# ADC.net
KiCad netlist of a schematic drawn in Altium Designer
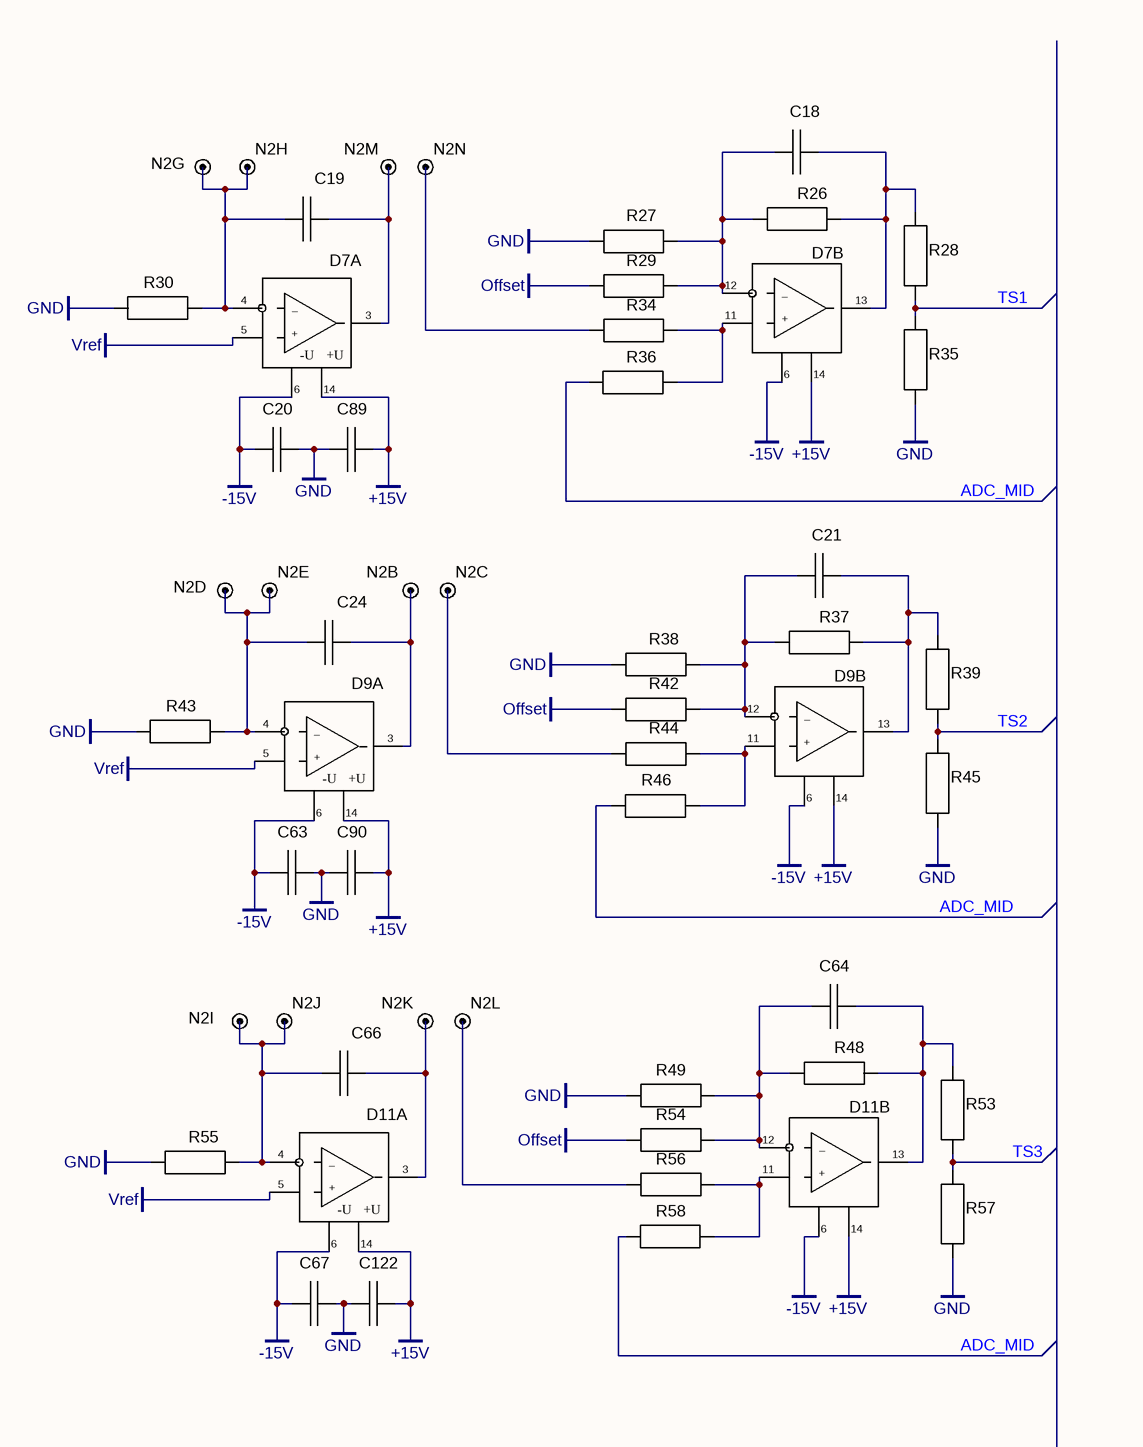
[diagram p0: ADC.SchDoc, top]
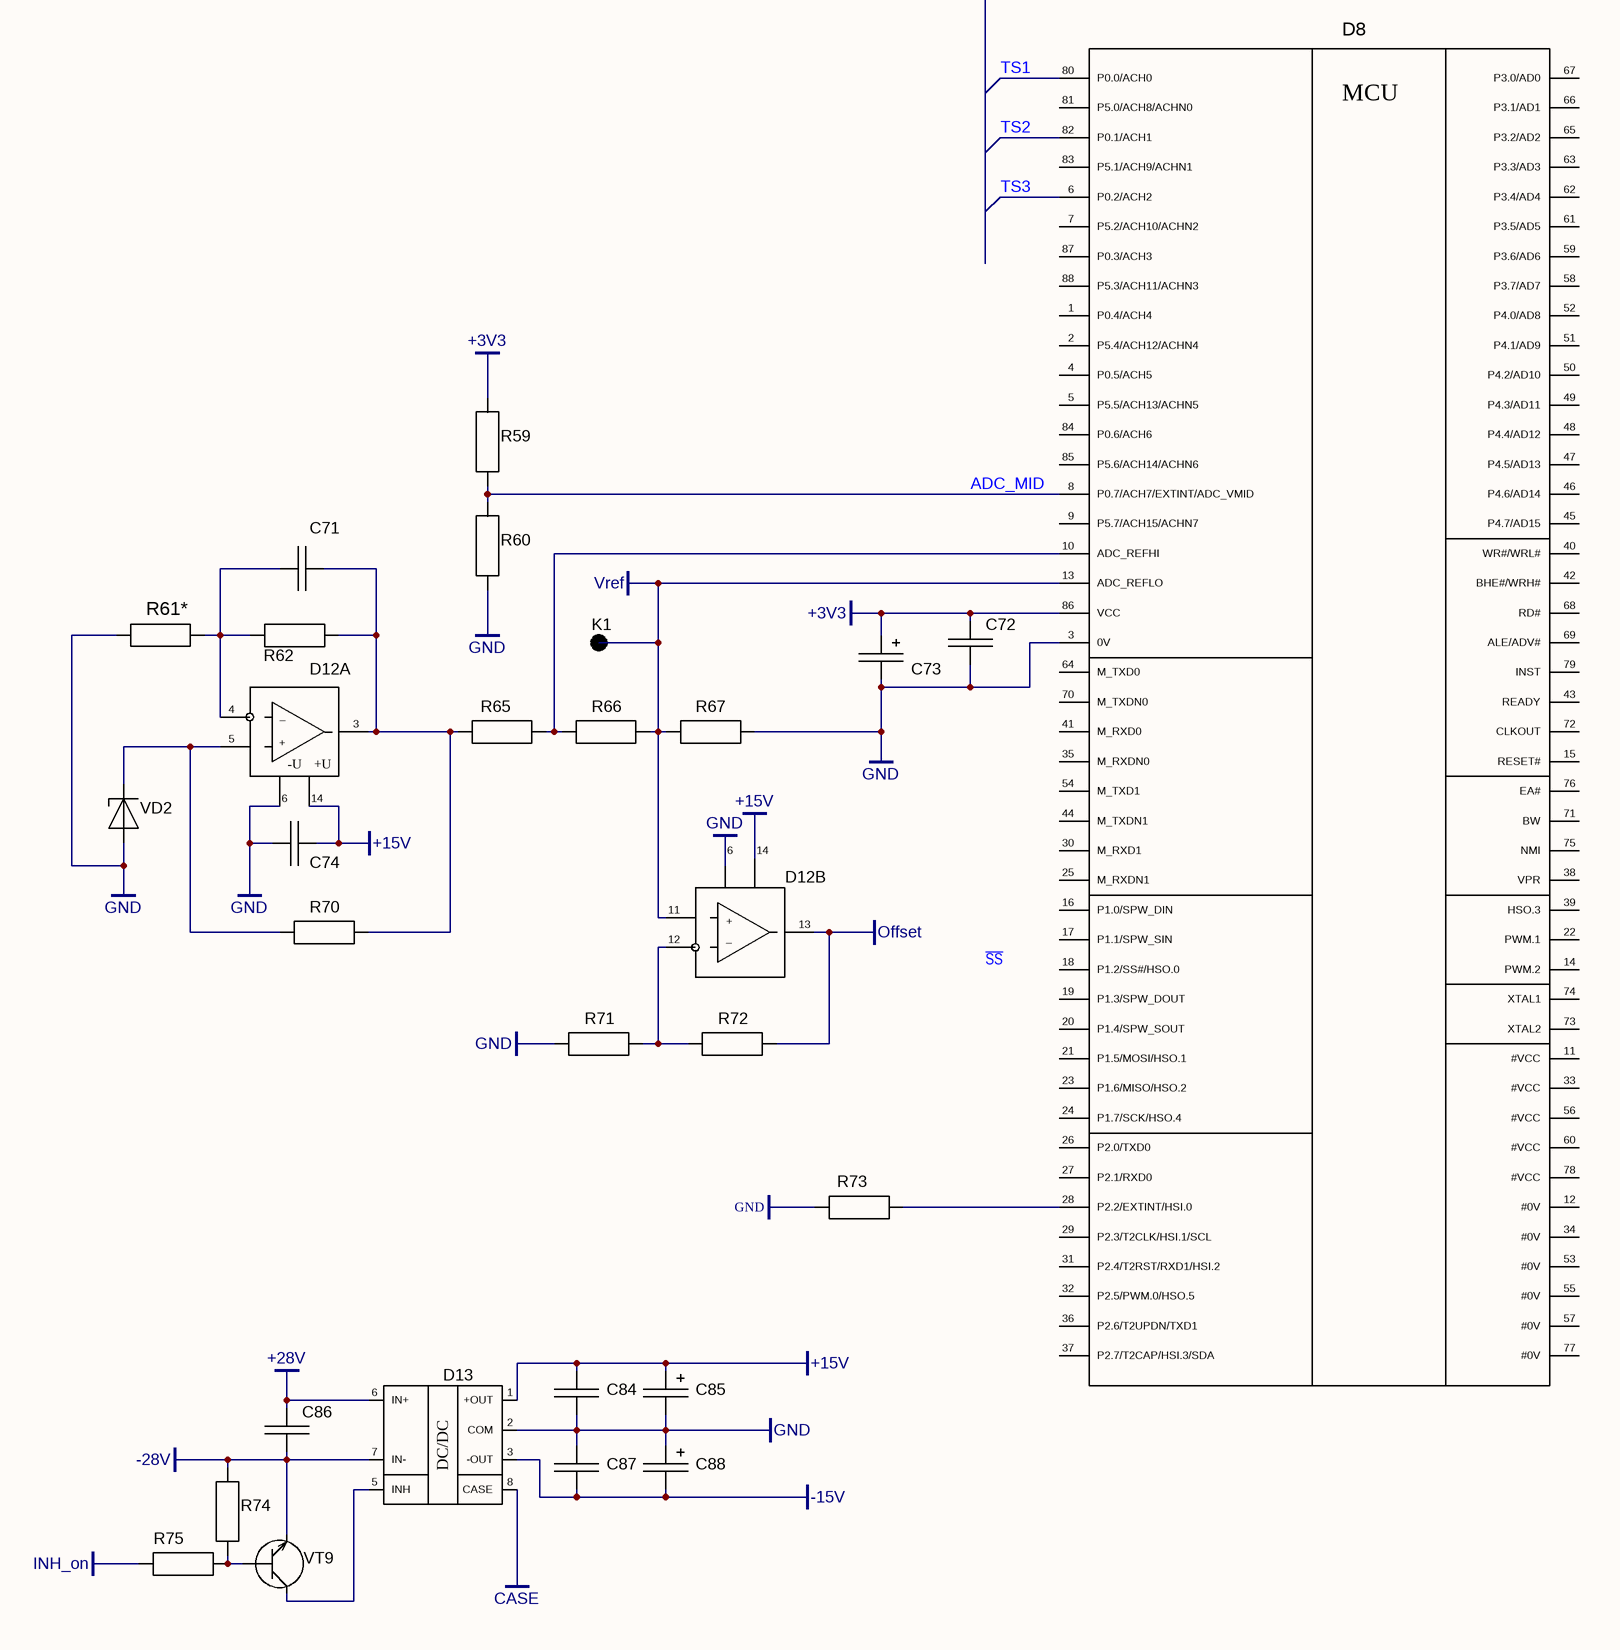
[diagram p1: ADC.SchDoc, bottom]

(export (version "E")
  (design (tool "Eeschema 10.0.6"))
  (components
    (comp (ref "C18")
      (value "~")
      (footprint "K1017V_4")
      (description "K10_17V_N50_4")
      (fields (field (name "PART NUMBER") "K10-17V-N50-0u015F"))
      (libsource (lib "Library") (part "K10_17V_N50_4"))
    )
    (comp (ref "C19")
      (value "~")
      (footprint "K1017V_4")
      (description "K10_17V_N50_4")
      (fields (field (name "PART NUMBER") "K10-17V-N50-0u015F"))
      (libsource (lib "Library") (part "K10_17V_N50_4"))
    )
    (comp (ref "C20")
      (value "~")
      (footprint "K1017V_4")
      (description "ChipCapasitor")
      (fields (field (name "PART NUMBER") "K10-17V-N90-0u068F"))
      (libsource (lib "Library") (part "K10_17V_N90_4"))
    )
    (comp (ref "C21")
      (value "~")
      (footprint "K1017V_4")
      (description "K10_17V_N50_4")
      (fields (field (name "PART NUMBER") "K10-17V-N50-0u015F"))
      (libsource (lib "Library") (part "K10_17V_N50_4"))
    )
    (comp (ref "C24")
      (value "~")
      (footprint "K1017V_4")
      (description "K10_17V_N50_4")
      (fields (field (name "PART NUMBER") "K10-17V-N50-0u015F"))
      (libsource (lib "Library") (part "K10_17V_N50_4"))
    )
    (comp (ref "C63")
      (value "~")
      (footprint "K1017V_4")
      (description "ChipCapasitor")
      (fields (field (name "PART NUMBER") "K10-17V-N90-0u068F"))
      (libsource (lib "Library") (part "K10_17V_N90_4"))
    )
    (comp (ref "C64")
      (value "~")
      (footprint "K1017V_4")
      (description "K10_17V_N50_4")
      (fields (field (name "PART NUMBER") "K10-17V-N50-0u015F"))
      (libsource (lib "Library") (part "K10_17V_N50_4"))
    )
    (comp (ref "C66")
      (value "~")
      (footprint "K1017V_4")
      (description "K10_17V_N50_4")
      (fields (field (name "PART NUMBER") "K10-17V-N50-0u015F"))
      (libsource (lib "Library") (part "K10_17V_N50_4"))
    )
    (comp (ref "C67")
      (value "~")
      (footprint "K1017V_4")
      (description "ChipCapasitor")
      (fields (field (name "PART NUMBER") "K10-17V-N90-0u068F"))
      (libsource (lib "Library") (part "K10_17V_N90_4"))
    )
    (comp (ref "C71")
      (value "~")
      (footprint "K1017V_4")
      (description "K10_17V_N50_4")
      (fields (field (name "PART NUMBER") "K10-17V-N50-0u015F"))
      (libsource (lib "Library") (part "K10_17V_N50_4"))
    )
    (comp (ref "C72")
      (value "~")
      (footprint "K1017V_4")
      (description "ChipCapasitor")
      (fields (field (name "PART NUMBER") "K10-17V-N90-0u068F"))
      (libsource (lib "Library") (part "K10_17V_N90_4"))
    )
    (comp (ref "C73")
      (value "~")
      (footprint "K53_56A_TYPE2")
      (description "TYPE2")
      (fields (field (name "PART NUMBER") "K53-56-6.3V-10uF±20"))
      (libsource (lib "Library") (part "K53_56A_TYPE2"))
    )
    (comp (ref "C74")
      (value "~")
      (footprint "K1017V_4")
      (description "ChipCapasitor")
      (fields (field (name "PART NUMBER") "K10-17V-N90-0u068F"))
      (libsource (lib "Library") (part "K10_17V_N90_4"))
    )
    (comp (ref "C84")
      (value "~")
      (footprint "K1017V_5")
      (description "K10_17V_N90_5")
      (fields (field (name "PART NUMBER") "K10-17V-N90-0u1F"))
      (libsource (lib "Library") (part "K10_17V_N90_5"))
    )
    (comp (ref "C85")
      (value "~")
      (footprint "K53_56A_TYPE3")
      (description "TYPE3")
      (fields (field (name "PART NUMBER") "K53-56-20V-10uF±20"))
      (libsource (lib "Library") (part "K53_56A_TYPE3"))
    )
    (comp (ref "C86")
      (value "~")
      (footprint "K1047V_3")
      (description "ChipCapasitor")
      (fields (field (name "PART NUMBER") "K10-47V-50V-0u47F"))
      (libsource (lib "Library") (part "K10_47V_50V_0.47uF"))
    )
    (comp (ref "C87")
      (value "~")
      (footprint "K1017V_5")
      (description "K10_17V_N90_5")
      (fields (field (name "PART NUMBER") "K10-17V-N90-0u1F"))
      (libsource (lib "Library") (part "K10_17V_N90_5"))
    )
    (comp (ref "C88")
      (value "~")
      (footprint "K53_56A_TYPE3")
      (description "TYPE3")
      (fields (field (name "PART NUMBER") "K53-56-20V-10uF±20"))
      (libsource (lib "Library") (part "K53_56A_TYPE3"))
    )
    (comp (ref "C89")
      (value "~")
      (footprint "K1017V_4")
      (description "ChipCapasitor")
      (fields (field (name "PART NUMBER") "K10-17V-N90-0u068F"))
      (libsource (lib "Library") (part "K10_17V_N90_4"))
    )
    (comp (ref "C90")
      (value "~")
      (footprint "K1017V_4")
      (description "ChipCapasitor")
      (fields (field (name "PART NUMBER") "K10-17V-N90-0u068F"))
      (libsource (lib "Library") (part "K10_17V_N90_4"))
    )
    (comp (ref "C122")
      (value "~")
      (footprint "K1017V_4")
      (description "ChipCapasitor")
      (fields (field (name "PART NUMBER") "K10-17V-N90-0u068F"))
      (libsource (lib "Library") (part "K10_17V_N90_4"))
    )
    (comp (ref "D7")
      (value "~")
      (footprint "H04_16_1B")
      (description "operational amplifier")
      (fields (field (name "PART NUMBER") "544UD16U3"))
      (libsource (lib "Library") (part "544UD16U3"))
    )
    (comp (ref "D8")
      (value "~")
      (footprint "4235_88_1_275")
      (description "16-bit microcontroller (based on MCS-96)")
      (fields
        (field (name "PART NUMBER") "1874VE7T")
        (field (name "COMPONENTLINK1URL") "C:\\AltiumLib\\pdf\\1874ВЕ7Т.pdf")
      )
      (libsource (lib "Library") (part "1874VE7T"))
    )
    (comp (ref "D9")
      (value "~")
      (footprint "H04_16_1B")
      (description "operational amplifier")
      (fields (field (name "PART NUMBER") "544UD16U3"))
      (libsource (lib "Library") (part "544UD16U3"))
    )
    (comp (ref "D11")
      (value "~")
      (footprint "H04_16_1B")
      (description "operational amplifier")
      (fields (field (name "PART NUMBER") "544UD16U3"))
      (libsource (lib "Library") (part "544UD16U3"))
    )
    (comp (ref "D12")
      (value "~")
      (footprint "H04_16_1B")
      (description "operational amplifier")
      (fields (field (name "PART NUMBER") "544UD16U3"))
      (libsource (lib "Library") (part "544UD16U3"))
    )
    (comp (ref "D13")
      (value "~")
      (footprint "SMSA2805S")
      (description "DC/DC 5W dual")
      (fields (field (name "PART NUMBER") "SMSA2815D_KR"))
      (libsource (lib "Library") (part "SMSA28xxD"))
    )
    (comp (ref "K1") (value "K") (footprint "K") (libsource (lib "Library") (part "K")))
    (comp (ref "N2")
      (value "~")
      (footprint "KOL26")
      (description "board analog SNP333-26")
      (fields (field (name "PART NUMBER") "bSNP333-26"))
      (libsource (lib "Library") (part "bSNP333-26"))
    )
    (comp (ref "R26")
      (value "~")
      (footprint "R1_8MP_0W125")
      (description "chip")
      (fields (field (name "PART NUMBER") "R1-8MP-0W125-1003±0,1"))
      (libsource (lib "Library") (part "R1_8MP_0W125"))
    )
    (comp (ref "R27")
      (value "~")
      (footprint "R1_8MP_0W125")
      (description "chip")
      (fields (field (name "PART NUMBER") "R1-8MP-0W125-2492±0,1"))
      (libsource (lib "Library") (part "R1_8MP_0W125"))
    )
    (comp (ref "R28")
      (value "~")
      (footprint "R1_8MP_0W125")
      (description "chip")
      (fields (field (name "PART NUMBER") "R1-8MP-0W125-2051±0,5"))
      (libsource (lib "Library") (part "R1_8MP_0W125"))
    )
    (comp (ref "R29")
      (value "~")
      (footprint "R1_8MP_0W125")
      (description "chip")
      (fields (field (name "PART NUMBER") "R1-8MP-0W125-2052±0,1"))
      (libsource (lib "Library") (part "R1_8MP_0W125"))
    )
    (comp (ref "R30")
      (value "~")
      (footprint "R1_8MP_0W125")
      (description "chip")
      (fields (field (name "PART NUMBER") "R1-8MP-0W125-1001±0,5"))
      (libsource (lib "Library") (part "R1_8MP_0W125"))
    )
    (comp (ref "R34")
      (value "~")
      (footprint "R1_8MP_0W125")
      (description "chip")
      (fields (field (name "PART NUMBER") "R1-8MP-0W125-2052±0,1"))
      (libsource (lib "Library") (part "R1_8MP_0W125"))
    )
    (comp (ref "R35")
      (value "~")
      (footprint "R1_8MP_0W125")
      (description "chip")
      (fields (field (name "PART NUMBER") "R1-8MP-0W125-5110±0,5"))
      (libsource (lib "Library") (part "R1_8MP_0W125"))
    )
    (comp (ref "R36")
      (value "~")
      (footprint "R1_8MP_0W125")
      (description "chip")
      (fields (field (name "PART NUMBER") "R1-8MP-0W125-2052±0,1"))
      (libsource (lib "Library") (part "R1_8MP_0W125"))
    )
    (comp (ref "R37")
      (value "~")
      (footprint "R1_8MP_0W125")
      (description "chip")
      (fields (field (name "PART NUMBER") "R1-8MP-0W125-1003±0,1"))
      (libsource (lib "Library") (part "R1_8MP_0W125"))
    )
    (comp (ref "R38")
      (value "~")
      (footprint "R1_8MP_0W125")
      (description "chip")
      (fields (field (name "PART NUMBER") "R1-8MP-0W125-2492±0,1"))
      (libsource (lib "Library") (part "R1_8MP_0W125"))
    )
    (comp (ref "R39")
      (value "~")
      (footprint "R1_8MP_0W125")
      (description "chip")
      (fields (field (name "PART NUMBER") "R1-8MP-0W125-2051±0,5"))
      (libsource (lib "Library") (part "R1_8MP_0W125"))
    )
    (comp (ref "R42")
      (value "~")
      (footprint "R1_8MP_0W125")
      (description "chip")
      (fields (field (name "PART NUMBER") "R1-8MP-0W125-2052±0,1"))
      (libsource (lib "Library") (part "R1_8MP_0W125"))
    )
    (comp (ref "R43")
      (value "~")
      (footprint "R1_8MP_0W125")
      (description "chip")
      (fields (field (name "PART NUMBER") "R1-8MP-0W125-1001±0,5"))
      (libsource (lib "Library") (part "R1_8MP_0W125"))
    )
    (comp (ref "R44")
      (value "~")
      (footprint "R1_8MP_0W125")
      (description "chip")
      (fields (field (name "PART NUMBER") "R1-8MP-0W125-2052±0,1"))
      (libsource (lib "Library") (part "R1_8MP_0W125"))
    )
    (comp (ref "R45")
      (value "~")
      (footprint "R1_8MP_0W125")
      (description "chip")
      (fields (field (name "PART NUMBER") "R1-8MP-0W125-5110±0,5"))
      (libsource (lib "Library") (part "R1_8MP_0W125"))
    )
    (comp (ref "R46")
      (value "~")
      (footprint "R1_8MP_0W125")
      (description "chip")
      (fields (field (name "PART NUMBER") "R1-8MP-0W125-2052±0,1"))
      (libsource (lib "Library") (part "R1_8MP_0W125"))
    )
    (comp (ref "R48")
      (value "~")
      (footprint "R1_8MP_0W125")
      (description "chip")
      (fields (field (name "PART NUMBER") "R1-8MP-0W125-1003±0,1"))
      (libsource (lib "Library") (part "R1_8MP_0W125"))
    )
    (comp (ref "R49")
      (value "~")
      (footprint "R1_8MP_0W125")
      (description "chip")
      (fields (field (name "PART NUMBER") "R1-8MP-0W125-2492±0,1"))
      (libsource (lib "Library") (part "R1_8MP_0W125"))
    )
    (comp (ref "R53")
      (value "~")
      (footprint "R1_8MP_0W125")
      (description "chip")
      (fields (field (name "PART NUMBER") "R1-8MP-0W125-2051±0,5"))
      (libsource (lib "Library") (part "R1_8MP_0W125"))
    )
    (comp (ref "R54")
      (value "~")
      (footprint "R1_8MP_0W125")
      (description "chip")
      (fields (field (name "PART NUMBER") "R1-8MP-0W125-2052±0,1"))
      (libsource (lib "Library") (part "R1_8MP_0W125"))
    )
    (comp (ref "R55")
      (value "~")
      (footprint "R1_8MP_0W125")
      (description "chip")
      (fields (field (name "PART NUMBER") "R1-8MP-0W125-1001±0,5"))
      (libsource (lib "Library") (part "R1_8MP_0W125"))
    )
    (comp (ref "R56")
      (value "~")
      (footprint "R1_8MP_0W125")
      (description "chip")
      (fields (field (name "PART NUMBER") "R1-8MP-0W125-2052±0,1"))
      (libsource (lib "Library") (part "R1_8MP_0W125"))
    )
    (comp (ref "R57")
      (value "~")
      (footprint "R1_8MP_0W125")
      (description "chip")
      (fields (field (name "PART NUMBER") "R1-8MP-0W125-5110±0,5"))
      (libsource (lib "Library") (part "R1_8MP_0W125"))
    )
    (comp (ref "R58")
      (value "~")
      (footprint "R1_8MP_0W125")
      (description "chip")
      (fields (field (name "PART NUMBER") "R1-8MP-0W125-2052±0,1"))
      (libsource (lib "Library") (part "R1_8MP_0W125"))
    )
    (comp (ref "R59")
      (value "~")
      (footprint "R1_112_W125")
      (description "chip")
      (fields
        (field (name "PART NUMBER") "R1-112-0W125-623±5")
        (field (name "COMPONENTLINK1URL") "C:\\AltiumLib\\pdf\\ТУ_Р1-112.pdf")
      )
      (libsource (lib "Library") (part "R1_112_0W125"))
    )
    (comp (ref "R60")
      (value "~")
      (footprint "R1_112_W125")
      (description "chip")
      (fields
        (field (name "PART NUMBER") "R1-112-0W125-623±5")
        (field (name "COMPONENTLINK1URL") "C:\\AltiumLib\\pdf\\ТУ_Р1-112.pdf")
      )
      (libsource (lib "Library") (part "R1_112_0W125"))
    )
    (comp (ref "R61*")
      (value "~")
      (footprint "C2_29V_0W125")
      (fields (field (name "PART NUMBER") "C2-29V-0W125-6491±0_1"))
      (libsource (lib "Library") (part "C2-29V"))
    )
    (comp (ref "R62")
      (value "~")
      (footprint "R1_8MP_0W125")
      (description "chip")
      (fields (field (name "PART NUMBER") "R1-8MP-0W125-3651±0,1"))
      (libsource (lib "Library") (part "R1_8MP_0W125"))
    )
    (comp (ref "R65")
      (value "~")
      (footprint "R1_8MP_0W125")
      (description "chip")
      (fields (field (name "PART NUMBER") "R1-8MP-0W125-7681±0,1"))
      (libsource (lib "Library") (part "R1_8MP_0W125"))
    )
    (comp (ref "R66")
      (value "~")
      (footprint "R1_8MP_0W125")
      (description "chip")
      (fields (field (name "PART NUMBER") "R1-8MP-0W125-1331±0,1"))
      (libsource (lib "Library") (part "R1_8MP_0W125"))
    )
    (comp (ref "R67")
      (value "~")
      (footprint "R1_8MP_0W125")
      (description "chip")
      (fields (field (name "PART NUMBER") "R1-8MP-0W125-1001±0,5"))
      (libsource (lib "Library") (part "R1_8MP_0W125"))
    )
    (comp (ref "R70")
      (value "~")
      (footprint "R1_8MP_0W125")
      (description "chip")
      (fields (field (name "PART NUMBER") "R1-8MP-0W125-4870±0,5"))
      (libsource (lib "Library") (part "R1_8MP_0W125"))
    )
    (comp (ref "R71")
      (value "~")
      (footprint "R1_8MP_0W125")
      (description "chip")
      (fields (field (name "PART NUMBER") "R1-8MP-0W125-1001±0,5"))
      (libsource (lib "Library") (part "R1_8MP_0W125"))
    )
    (comp (ref "R72")
      (value "~")
      (footprint "R1_8MP_0W125")
      (description "chip")
      (fields (field (name "PART NUMBER") "R1-8MP-0W125-2801±0,5"))
      (libsource (lib "Library") (part "R1_8MP_0W125"))
    )
    (comp (ref "R73")
      (value "~")
      (footprint "R1_112_W125")
      (description "chip")
      (fields
        (field (name "PART NUMBER") "R1-112-0W125-101±5")
        (field (name "COMPONENTLINK1URL") "C:\\AltiumLib\\pdf\\ТУ_Р1-112.pdf")
      )
      (libsource (lib "Library") (part "R1_112_0W125"))
    )
    (comp (ref "R74")
      (value "~")
      (footprint "R1_112_W125")
      (description "chip")
      (fields
        (field (name "PART NUMBER") "R1-112-0W125-302±5")
        (field (name "COMPONENTLINK1URL") "C:\\AltiumLib\\pdf\\ТУ_Р1-112.pdf")
      )
      (libsource (lib "Library") (part "R1_112_0W125"))
    )
    (comp (ref "R75")
      (value "~")
      (footprint "R1_112_W125")
      (description "chip")
      (fields
        (field (name "PART NUMBER") "R1-112-0W125-273±5")
        (field (name "COMPONENTLINK1URL") "C:\\AltiumLib\\pdf\\ТУ_Р1-112.pdf")
      )
      (libsource (lib "Library") (part "R1_112_0W125"))
    )
    (comp (ref "VD2")
      (value "~")
      (footprint "2S222G")
      (fields (field (name "PART NUMBER") "2S108D"))
      (libsource (lib "Library") (part "2S108D"))
    )
    (comp (ref "VT9")
      (value "2T665A91")
      (footprint "2T665A91")
      (description "n-p-n")
      (libsource (lib "Library") (part "2T665A91"))
    )
  )
  (nets
    (net (code "1") (name "+3V3") (class "Default")
      (node (ref "C72") (pin "2") (pintype "passive"))
      (node (ref "C73") (pin "Plus") (pinfunction "Plus_Plus") (pintype "passive"))
      (node (ref "D8") (pin "86") (pinfunction "VCC_86") (pintype "passive"))
      (node (ref "R59") (pin "2") (pintype "passive"))
    )
    (net (code "2") (name "+15V") (class "Default")
      (node (ref "C122") (pin "2") (pintype "passive"))
      (node (ref "C74") (pin "1") (pintype "passive"))
      (node (ref "C84") (pin "2") (pintype "passive"))
      (node (ref "C85") (pin "Plus") (pinfunction "Plus_Plus") (pintype "passive"))
      (node (ref "C89") (pin "2") (pintype "passive"))
      (node (ref "C90") (pin "2") (pintype "passive"))
      (node (ref "D11") (pin "14") (pinfunction "+U_14") (pintype "power_in"))
      (node (ref "D12") (pin "14") (pinfunction "+U_14") (pintype "power_in"))
      (node (ref "D13") (pin "1") (pinfunction "+OUT_1") (pintype "passive"))
      (node (ref "D7") (pin "14") (pinfunction "+U_14") (pintype "power_in"))
      (node (ref "D9") (pin "14") (pinfunction "+U_14") (pintype "power_in"))
    )
    (net (code "3") (name "+28V") (class "Default")
      (node (ref "C86") (pin "2") (pintype "passive"))
      (node (ref "D13") (pin "6") (pinfunction "IN+_6") (pintype "passive"))
    )
    (net (code "4") (name "-15V") (class "Default")
      (node (ref "C20") (pin "1") (pintype "passive"))
      (node (ref "C63") (pin "1") (pintype "passive"))
      (node (ref "C67") (pin "1") (pintype "passive"))
      (node (ref "C87") (pin "1") (pintype "passive"))
      (node (ref "C88") (pin "Minus") (pinfunction "Minus_Minus") (pintype "passive"))
      (node (ref "D11") (pin "6") (pinfunction "-U_6") (pintype "power_in"))
      (node (ref "D13") (pin "3") (pinfunction "-OUT_3") (pintype "passive"))
      (node (ref "D7") (pin "6") (pinfunction "-U_6") (pintype "power_in"))
      (node (ref "D9") (pin "6") (pinfunction "-U_6") (pintype "power_in"))
    )
    (net (code "5") (name "-28V") (class "Default")
      (node (ref "C86") (pin "1") (pintype "passive"))
      (node (ref "D13") (pin "7") (pinfunction "IN-_7") (pintype "passive"))
      (node (ref "R74") (pin "2") (pintype "passive"))
      (node (ref "VT9") (pin "E") (pinfunction "E_E") (pintype "passive"))
    )
    (net (code "6") (name "/ADC_MID") (class "Default")
      (node (ref "D8") (pin "8") (pinfunction "P0.7/ACH7/EXTINT/ADC_VMID_8") (pintype "passive"))
      (node (ref "R36") (pin "2") (pintype "passive"))
      (node (ref "R46") (pin "2") (pintype "passive"))
      (node (ref "R58") (pin "2") (pintype "passive"))
      (node (ref "R59") (pin "1") (pintype "passive"))
      (node (ref "R60") (pin "2") (pintype "passive"))
    )
    (net (code "8") (name "/TS1") (class "Default")
      (node (ref "D8") (pin "80") (pinfunction "P0.0/ACH0_80") (pintype "passive"))
      (node (ref "R28") (pin "1") (pintype "passive"))
      (node (ref "R35") (pin "2") (pintype "passive"))
    )
    (net (code "9") (name "/TS2") (class "Default")
      (node (ref "D8") (pin "82") (pinfunction "P0.1/ACH1_82") (pintype "passive"))
      (node (ref "R39") (pin "1") (pintype "passive"))
      (node (ref "R45") (pin "2") (pintype "passive"))
    )
    (net (code "10") (name "/TS3") (class "Default")
      (node (ref "D8") (pin "6") (pinfunction "P0.2/ACH2_6") (pintype "passive"))
      (node (ref "R53") (pin "1") (pintype "passive"))
      (node (ref "R57") (pin "2") (pintype "passive"))
    )
    (net (code "11") (name "CASE") (class "Default")
      (node (ref "D13") (pin "8") (pinfunction "CASE_8") (pintype "passive"))
    )
    (net (code "12") (name "GND") (class "Default")
      (node (ref "C122") (pin "1") (pintype "passive"))
      (node (ref "C20") (pin "2") (pintype "passive"))
      (node (ref "C63") (pin "2") (pintype "passive"))
      (node (ref "C67") (pin "2") (pintype "passive"))
      (node (ref "C72") (pin "1") (pintype "passive"))
      (node (ref "C73") (pin "Minus") (pinfunction "Minus_Minus") (pintype "passive"))
      (node (ref "C74") (pin "2") (pintype "passive"))
      (node (ref "C84") (pin "1") (pintype "passive"))
      (node (ref "C85") (pin "Minus") (pinfunction "Minus_Minus") (pintype "passive"))
      (node (ref "C87") (pin "2") (pintype "passive"))
      (node (ref "C88") (pin "Plus") (pinfunction "Plus_Plus") (pintype "passive"))
      (node (ref "C89") (pin "1") (pintype "passive"))
      (node (ref "C90") (pin "1") (pintype "passive"))
      (node (ref "D12") (pin "6") (pinfunction "-U_6") (pintype "power_in"))
      (node (ref "D13") (pin "2") (pinfunction "COM_2") (pintype "passive"))
      (node (ref "D8") (pin "3") (pinfunction "0V_3") (pintype "passive"))
      (node (ref "R27") (pin "1") (pintype "passive"))
      (node (ref "R30") (pin "2") (pintype "passive"))
      (node (ref "R35") (pin "1") (pintype "passive"))
      (node (ref "R38") (pin "1") (pintype "passive"))
      (node (ref "R43") (pin "2") (pintype "passive"))
      (node (ref "R45") (pin "1") (pintype "passive"))
      (node (ref "R49") (pin "1") (pintype "passive"))
      (node (ref "R55") (pin "2") (pintype "passive"))
      (node (ref "R57") (pin "1") (pintype "passive"))
      (node (ref "R60") (pin "1") (pintype "passive"))
      (node (ref "R61*") (pin "1") (pinfunction "i/o_1") (pintype "passive"))
      (node (ref "R67") (pin "2") (pintype "passive"))
      (node (ref "R71") (pin "2") (pintype "passive"))
      (node (ref "R73") (pin "1") (pintype "passive"))
      (node (ref "VD2") (pin "A") (pintype "passive"))
    )
    (net (code "13") (name "INH_on") (class "Default") (node (ref "R75") (pin "1") (pintype "passive")))
    (net (code "14") (name "Net-(D7A-IN-)") (class "Default")
      (node (ref "C19") (pin "1") (pintype "passive"))
      (node (ref "D7") (pin "4") (pinfunction "IN-_4") (pintype "passive"))
      (node (ref "N2") (pin "7") (pintype "passive"))
      (node (ref "N2") (pin "8") (pintype "passive"))
      (node (ref "R30") (pin "1") (pintype "passive"))
    )
    (net (code "15") (name "Net-(D7A-OUT)") (class "Default")
      (node (ref "C19") (pin "2") (pintype "passive"))
      (node (ref "D7") (pin "3") (pinfunction "OUT_3") (pintype "passive"))
      (node (ref "N2") (pin "13") (pintype "passive"))
    )
    (net (code "16") (name "Net-(D7B-IN+)") (class "Default")
      (node (ref "D7") (pin "11") (pinfunction "IN+_11") (pintype "passive"))
      (node (ref "R34") (pin "2") (pintype "passive"))
      (node (ref "R36") (pin "1") (pintype "passive"))
    )
    (net (code "17") (name "Net-(D7B-IN-)") (class "Default")
      (node (ref "C18") (pin "1") (pintype "passive"))
      (node (ref "D7") (pin "12") (pinfunction "IN-_12") (pintype "passive"))
      (node (ref "R26") (pin "1") (pintype "passive"))
      (node (ref "R27") (pin "2") (pintype "passive"))
      (node (ref "R29") (pin "2") (pintype "passive"))
    )
    (net (code "18") (name "Net-(D7B-OUT)") (class "Default")
      (node (ref "C18") (pin "2") (pintype "passive"))
      (node (ref "D7") (pin "13") (pinfunction "OUT_13") (pintype "passive"))
      (node (ref "R26") (pin "2") (pintype "passive"))
      (node (ref "R28") (pin "2") (pintype "passive"))
    )
    (net (code "19") (name "Net-(D8-ADC_REFHI)") (class "Default")
      (node (ref "D8") (pin "10") (pinfunction "ADC_REFHI_10") (pintype "passive"))
      (node (ref "R65") (pin "1") (pintype "passive"))
      (node (ref "R66") (pin "2") (pintype "passive"))
    )
    (net (code "20") (name "Net-(D8-P2.2{slash}EXTINT{slash}HSI.0)") (class "Default")
      (node (ref "D8") (pin "28") (pinfunction "P2.2/EXTINT/HSI.0_28") (pintype "passive"))
      (node (ref "R73") (pin "2") (pintype "passive"))
    )
    (net (code "21") (name "Net-(D9A-IN-)") (class "Default")
      (node (ref "C24") (pin "1") (pintype "passive"))
      (node (ref "D9") (pin "4") (pinfunction "IN-_4") (pintype "passive"))
      (node (ref "N2") (pin "4") (pintype "passive"))
      (node (ref "N2") (pin "5") (pintype "passive"))
      (node (ref "R43") (pin "1") (pintype "passive"))
    )
    (net (code "22") (name "Net-(D9A-OUT)") (class "Default")
      (node (ref "C24") (pin "2") (pintype "passive"))
      (node (ref "D9") (pin "3") (pinfunction "OUT_3") (pintype "passive"))
      (node (ref "N2") (pin "2") (pintype "passive"))
    )
    (net (code "23") (name "Net-(D9B-IN+)") (class "Default")
      (node (ref "D9") (pin "11") (pinfunction "IN+_11") (pintype "passive"))
      (node (ref "R44") (pin "2") (pintype "passive"))
      (node (ref "R46") (pin "1") (pintype "passive"))
    )
    (net (code "24") (name "Net-(D9B-IN-)") (class "Default")
      (node (ref "C21") (pin "1") (pintype "passive"))
      (node (ref "D9") (pin "12") (pinfunction "IN-_12") (pintype "passive"))
      (node (ref "R37") (pin "1") (pintype "passive"))
      (node (ref "R38") (pin "2") (pintype "passive"))
      (node (ref "R42") (pin "2") (pintype "passive"))
    )
    (net (code "25") (name "Net-(D9B-OUT)") (class "Default")
      (node (ref "C21") (pin "2") (pintype "passive"))
      (node (ref "D9") (pin "13") (pinfunction "OUT_13") (pintype "passive"))
      (node (ref "R37") (pin "2") (pintype "passive"))
      (node (ref "R39") (pin "2") (pintype "passive"))
    )
    (net (code "26") (name "Net-(D11A-IN-)") (class "Default")
      (node (ref "C66") (pin "1") (pintype "passive"))
      (node (ref "D11") (pin "4") (pinfunction "IN-_4") (pintype "passive"))
      (node (ref "N2") (pin "10") (pintype "passive"))
      (node (ref "N2") (pin "9") (pintype "passive"))
      (node (ref "R55") (pin "1") (pintype "passive"))
    )
    (net (code "27") (name "Net-(D11A-OUT)") (class "Default")
      (node (ref "C66") (pin "2") (pintype "passive"))
      (node (ref "D11") (pin "3") (pinfunction "OUT_3") (pintype "passive"))
      (node (ref "N2") (pin "11") (pintype "passive"))
    )
    (net (code "28") (name "Net-(D11B-IN+)") (class "Default")
      (node (ref "D11") (pin "11") (pinfunction "IN+_11") (pintype "passive"))
      (node (ref "R56") (pin "2") (pintype "passive"))
      (node (ref "R58") (pin "1") (pintype "passive"))
    )
    (net (code "29") (name "Net-(D11B-IN-)") (class "Default")
      (node (ref "C64") (pin "1") (pintype "passive"))
      (node (ref "D11") (pin "12") (pinfunction "IN-_12") (pintype "passive"))
      (node (ref "R48") (pin "1") (pintype "passive"))
      (node (ref "R49") (pin "2") (pintype "passive"))
      (node (ref "R54") (pin "2") (pintype "passive"))
    )
    (net (code "30") (name "Net-(D11B-OUT)") (class "Default")
      (node (ref "C64") (pin "2") (pintype "passive"))
      (node (ref "D11") (pin "13") (pinfunction "OUT_13") (pintype "passive"))
      (node (ref "R48") (pin "2") (pintype "passive"))
      (node (ref "R53") (pin "2") (pintype "passive"))
    )
    (net (code "31") (name "Net-(D12A-IN+)") (class "Default")
      (node (ref "D12") (pin "5") (pinfunction "IN+_5") (pintype "passive"))
      (node (ref "R70") (pin "1") (pintype "passive"))
      (node (ref "VD2") (pin "C") (pintype "passive"))
    )
    (net (code "32") (name "Net-(D12A-IN-)") (class "Default")
      (node (ref "C71") (pin "1") (pintype "passive"))
      (node (ref "D12") (pin "4") (pinfunction "IN-_4") (pintype "passive"))
      (node (ref "R61*") (pin "2") (pinfunction "i/o_2") (pintype "passive"))
      (node (ref "R62") (pin "1") (pintype "passive"))
    )
    (net (code "33") (name "Net-(D12A-OUT)") (class "Default")
      (node (ref "C71") (pin "2") (pintype "passive"))
      (node (ref "D12") (pin "3") (pinfunction "OUT_3") (pintype "passive"))
      (node (ref "R62") (pin "2") (pintype "passive"))
      (node (ref "R65") (pin "2") (pintype "passive"))
      (node (ref "R70") (pin "2") (pintype "passive"))
    )
    (net (code "34") (name "Net-(D12B-IN-)") (class "Default")
      (node (ref "D12") (pin "12") (pinfunction "IN-_12") (pintype "passive"))
      (node (ref "R71") (pin "1") (pintype "passive"))
      (node (ref "R72") (pin "2") (pintype "passive"))
    )
    (net (code "35") (name "Net-(D13-INH)") (class "Default")
      (node (ref "D13") (pin "5") (pinfunction "INH_5") (pintype "passive"))
      (node (ref "VT9") (pin "C") (pinfunction "C_C") (pintype "passive"))
    )
    (net (code "36") (name "Net-(N2-Pad3)") (class "Default")
      (node (ref "N2") (pin "3") (pintype "passive"))
      (node (ref "R44") (pin "1") (pintype "passive"))
    )
    (net (code "37") (name "Net-(N2-Pad12)") (class "Default")
      (node (ref "N2") (pin "12") (pintype "passive"))
      (node (ref "R56") (pin "1") (pintype "passive"))
    )
    (net (code "38") (name "Net-(N2-Pad14)") (class "Default")
      (node (ref "N2") (pin "14") (pintype "passive"))
      (node (ref "R34") (pin "1") (pintype "passive"))
    )
    (net (code "39") (name "Net-(R74-Pad1)") (class "Default")
      (node (ref "R74") (pin "1") (pintype "passive"))
      (node (ref "R75") (pin "2") (pintype "passive"))
      (node (ref "VT9") (pin "B") (pinfunction "B_B") (pintype "passive"))
    )
    (net (code "40") (name "Offset") (class "Default")
      (node (ref "D12") (pin "13") (pinfunction "OUT_13") (pintype "passive"))
      (node (ref "R29") (pin "1") (pintype "passive"))
      (node (ref "R42") (pin "1") (pintype "passive"))
      (node (ref "R54") (pin "1") (pintype "passive"))
      (node (ref "R72") (pin "1") (pintype "passive"))
    )
    (net (code "41") (name "Vref") (class "Default")
      (node (ref "D11") (pin "5") (pinfunction "IN+_5") (pintype "passive"))
      (node (ref "D12") (pin "11") (pinfunction "IN+_11") (pintype "passive"))
      (node (ref "D7") (pin "5") (pinfunction "IN+_5") (pintype "passive"))
      (node (ref "D8") (pin "13") (pinfunction "ADC_REFLO_13") (pintype "passive"))
      (node (ref "D9") (pin "5") (pinfunction "IN+_5") (pintype "passive"))
      (node (ref "K1") (pin "1") (pintype "passive"))
      (node (ref "R66") (pin "1") (pintype "passive"))
      (node (ref "R67") (pin "1") (pintype "passive"))
    )
    (net (code "42") (name "unconnected-(D7-Pad1)") (class "Default")
      (node (ref "D7") (pin "1") (pinfunction "1_1") (pintype "passive"))
    )
    (net (code "43") (name "unconnected-(D7-Pad1)_1") (class "Default")
      (node (ref "D7") (pin "1") (pinfunction "1_1") (pintype "passive"))
    )
    (net (code "44") (name "unconnected-(D7-Pad2)") (class "Default")
      (node (ref "D7") (pin "2") (pinfunction "2_2") (pintype "passive"))
    )
    (net (code "45") (name "unconnected-(D7-Pad2)_1") (class "Default")
      (node (ref "D7") (pin "2") (pinfunction "2_2") (pintype "passive"))
    )
    (net (code "46") (name "unconnected-(D7-Pad7)") (class "Default")
      (node (ref "D7") (pin "7") (pinfunction "7_7") (pintype "passive"))
    )
    (net (code "47") (name "unconnected-(D7-Pad7)_1") (class "Default")
      (node (ref "D7") (pin "7") (pinfunction "7_7") (pintype "passive"))
    )
    (net (code "48") (name "unconnected-(D7-Pad8)") (class "Default")
      (node (ref "D7") (pin "8") (pinfunction "8_8") (pintype "passive"))
    )
    (net (code "49") (name "unconnected-(D7-Pad8)_1") (class "Default")
      (node (ref "D7") (pin "8") (pinfunction "8_8") (pintype "passive"))
    )
    (net (code "50") (name "unconnected-(D7-Pad9)") (class "Default")
      (node (ref "D7") (pin "9") (pinfunction "9_9") (pintype "passive"))
    )
    (net (code "51") (name "unconnected-(D7-Pad9)_1") (class "Default")
      (node (ref "D7") (pin "9") (pinfunction "9_9") (pintype "passive"))
    )
    (net (code "52") (name "unconnected-(D7-Pad10)") (class "Default")
      (node (ref "D7") (pin "10") (pinfunction "10_10") (pintype "passive"))
    )
    (net (code "53") (name "unconnected-(D7-Pad10)_1") (class "Default")
      (node (ref "D7") (pin "10") (pinfunction "10_10") (pintype "passive"))
    )
    (net (code "54") (name "unconnected-(D7-Pad15)") (class "Default")
      (node (ref "D7") (pin "15") (pinfunction "15_15") (pintype "passive"))
    )
    (net (code "55") (name "unconnected-(D7-Pad15)_1") (class "Default")
      (node (ref "D7") (pin "15") (pinfunction "15_15") (pintype "passive"))
    )
    (net (code "56") (name "unconnected-(D7-Pad16)") (class "Default")
      (node (ref "D7") (pin "16") (pinfunction "16_16") (pintype "passive"))
    )
    (net (code "57") (name "unconnected-(D7-Pad16)_1") (class "Default")
      (node (ref "D7") (pin "16") (pinfunction "16_16") (pintype "passive"))
    )
    (net (code "58") (name "unconnected-(D8-#0V-Pad12)") (class "Default")
      (node (ref "D8") (pin "12") (pinfunction "#0V_12") (pintype "passive"))
    )
    (net (code "59") (name "unconnected-(D8-#0V-Pad34)") (class "Default")
      (node (ref "D8") (pin "34") (pinfunction "#0V_34") (pintype "passive"))
    )
    (net (code "60") (name "unconnected-(D8-#0V-Pad53)") (class "Default")
      (node (ref "D8") (pin "53") (pinfunction "#0V_53") (pintype "passive"))
    )
    (net (code "61") (name "unconnected-(D8-#0V-Pad55)") (class "Default")
      (node (ref "D8") (pin "55") (pinfunction "#0V_55") (pintype "passive"))
    )
    (net (code "62") (name "unconnected-(D8-#0V-Pad57)") (class "Default")
      (node (ref "D8") (pin "57") (pinfunction "#0V_57") (pintype "passive"))
    )
    (net (code "63") (name "unconnected-(D8-#0V-Pad77)") (class "Default")
      (node (ref "D8") (pin "77") (pinfunction "#0V_77") (pintype "passive"))
    )
    (net (code "64") (name "unconnected-(D8-#VCC-Pad11)") (class "Default")
      (node (ref "D8") (pin "11") (pinfunction "#VCC_11") (pintype "passive"))
    )
    (net (code "65") (name "unconnected-(D8-#VCC-Pad33)") (class "Default")
      (node (ref "D8") (pin "33") (pinfunction "#VCC_33") (pintype "passive"))
    )
    (net (code "66") (name "unconnected-(D8-#VCC-Pad56)") (class "Default")
      (node (ref "D8") (pin "56") (pinfunction "#VCC_56") (pintype "passive"))
    )
    (net (code "67") (name "unconnected-(D8-#VCC-Pad60)") (class "Default")
      (node (ref "D8") (pin "60") (pinfunction "#VCC_60") (pintype "passive"))
    )
    (net (code "68") (name "unconnected-(D8-#VCC-Pad78)") (class "Default")
      (node (ref "D8") (pin "78") (pinfunction "#VCC_78") (pintype "passive"))
    )
    (net (code "69") (name "unconnected-(D8-ALE{slash}ADV#-Pad69)") (class "Default")
      (node (ref "D8") (pin "69") (pinfunction "ALE/ADV#_69") (pintype "passive"))
    )
    (net (code "70") (name "unconnected-(D8-BHE#{slash}WRH#-Pad42)") (class "Default")
      (node (ref "D8") (pin "42") (pinfunction "BHE#/WRH#_42") (pintype "passive"))
    )
    (net (code "71") (name "unconnected-(D8-BW-Pad71)") (class "Default")
      (node (ref "D8") (pin "71") (pinfunction "BW_71") (pintype "passive"))
    )
    (net (code "72") (name "unconnected-(D8-CLKOUT-Pad72)") (class "Default")
      (node (ref "D8") (pin "72") (pinfunction "CLKOUT_72") (pintype "passive"))
    )
    (net (code "73") (name "unconnected-(D8-EA#-Pad76)") (class "Default")
      (node (ref "D8") (pin "76") (pinfunction "EA#_76") (pintype "passive"))
    )
    (net (code "74") (name "unconnected-(D8-HSO.3-Pad39)") (class "Default")
      (node (ref "D8") (pin "39") (pinfunction "HSO.3_39") (pintype "passive"))
    )
    (net (code "75") (name "unconnected-(D8-INST-Pad79)") (class "Default")
      (node (ref "D8") (pin "79") (pinfunction "INST_79") (pintype "passive"))
    )
    (net (code "76") (name "unconnected-(D8-M_RXD0-Pad41)") (class "Default")
      (node (ref "D8") (pin "41") (pinfunction "M_RXD0_41") (pintype "passive"))
    )
    (net (code "77") (name "unconnected-(D8-M_RXD1-Pad30)") (class "Default")
      (node (ref "D8") (pin "30") (pinfunction "M_RXD1_30") (pintype "passive"))
    )
    (net (code "78") (name "unconnected-(D8-M_RXDN0-Pad35)") (class "Default")
      (node (ref "D8") (pin "35") (pinfunction "M_RXDN0_35") (pintype "passive"))
    )
    (net (code "79") (name "unconnected-(D8-M_RXDN1-Pad25)") (class "Default")
      (node (ref "D8") (pin "25") (pinfunction "M_RXDN1_25") (pintype "passive"))
    )
    (net (code "80") (name "unconnected-(D8-M_TXD0-Pad64)") (class "Default")
      (node (ref "D8") (pin "64") (pinfunction "M_TXD0_64") (pintype "passive"))
    )
    (net (code "81") (name "unconnected-(D8-M_TXD1-Pad54)") (class "Default")
      (node (ref "D8") (pin "54") (pinfunction "M_TXD1_54") (pintype "passive"))
    )
    (net (code "82") (name "unconnected-(D8-M_TXDN0-Pad70)") (class "Default")
      (node (ref "D8") (pin "70") (pinfunction "M_TXDN0_70") (pintype "passive"))
    )
    (net (code "83") (name "unconnected-(D8-M_TXDN1-Pad44)") (class "Default")
      (node (ref "D8") (pin "44") (pinfunction "M_TXDN1_44") (pintype "passive"))
    )
    (net (code "84") (name "unconnected-(D8-NMI-Pad75)") (class "Default")
      (node (ref "D8") (pin "75") (pinfunction "NMI_75") (pintype "passive"))
    )
    (net (code "85") (name "unconnected-(D8-P0.3{slash}ACH3-Pad87)") (class "Default")
      (node (ref "D8") (pin "87") (pinfunction "P0.3/ACH3_87") (pintype "passive"))
    )
    (net (code "86") (name "unconnected-(D8-P0.4{slash}ACH4-Pad1)") (class "Default")
      (node (ref "D8") (pin "1") (pinfunction "P0.4/ACH4_1") (pintype "passive"))
    )
    (net (code "87") (name "unconnected-(D8-P0.5{slash}ACH5-Pad4)") (class "Default")
      (node (ref "D8") (pin "4") (pinfunction "P0.5/ACH5_4") (pintype "passive"))
    )
    (net (code "88") (name "unconnected-(D8-P0.6{slash}ACH6-Pad84)") (class "Default")
      (node (ref "D8") (pin "84") (pinfunction "P0.6/ACH6_84") (pintype "passive"))
    )
    (net (code "89") (name "unconnected-(D8-P1.0{slash}SPW_DIN-Pad16)") (class "Default")
      (node (ref "D8") (pin "16") (pinfunction "P1.0/SPW_DIN_16") (pintype "passive"))
    )
    (net (code "90") (name "unconnected-(D8-P1.1{slash}SPW_SIN-Pad17)") (class "Default")
      (node (ref "D8") (pin "17") (pinfunction "P1.1/SPW_SIN_17") (pintype "passive"))
    )
    (net (code "91") (name "unconnected-(D8-P1.2{slash}SS#{slash}HSO.0-Pad18)") (class "Default")
      (node (ref "D8") (pin "18") (pinfunction "P1.2/SS#/HSO.0_18") (pintype "passive"))
    )
    (net (code "92") (name "unconnected-(D8-P1.3{slash}SPW_DOUT-Pad19)") (class "Default")
      (node (ref "D8") (pin "19") (pinfunction "P1.3/SPW_DOUT_19") (pintype "passive"))
    )
    (net (code "93") (name "unconnected-(D8-P1.4{slash}SPW_SOUT-Pad20)") (class "Default")
      (node (ref "D8") (pin "20") (pinfunction "P1.4/SPW_SOUT_20") (pintype "passive"))
    )
    (net (code "94") (name "unconnected-(D8-P1.5{slash}MOSI{slash}HSO.1-Pad21)") (class "Default")
      (node (ref "D8") (pin "21") (pinfunction "P1.5/MOSI/HSO.1_21") (pintype "passive"))
    )
    (net (code "95") (name "unconnected-(D8-P1.6{slash}MISO{slash}HSO.2-Pad23)") (class "Default")
      (node (ref "D8") (pin "23") (pinfunction "P1.6/MISO/HSO.2_23") (pintype "passive"))
    )
    (net (code "96") (name "unconnected-(D8-P1.7{slash}SCK{slash}HSO.4-Pad24)") (class "Default")
      (node (ref "D8") (pin "24") (pinfunction "P1.7/SCK/HSO.4_24") (pintype "passive"))
    )
    (net (code "97") (name "unconnected-(D8-P2.0{slash}TXD0-Pad26)") (class "Default")
      (node (ref "D8") (pin "26") (pinfunction "P2.0/TXD0_26") (pintype "passive"))
    )
    (net (code "98") (name "unconnected-(D8-P2.1{slash}RXD0-Pad27)") (class "Default")
      (node (ref "D8") (pin "27") (pinfunction "P2.1/RXD0_27") (pintype "passive"))
    )
    (net (code "99") (name "unconnected-(D8-P2.3{slash}T2CLK{slash}HSI.1{slash}SCL-Pad29)") (class "Default")
      (node (ref "D8") (pin "29") (pinfunction "P2.3/T2CLK/HSI.1/SCL_29") (pintype "passive"))
    )
    (net (code "100") (name "unconnected-(D8-P2.4{slash}T2RST{slash}RXD1{slash}HSI.2-Pad31)") (class "Default")
      (node (ref "D8") (pin "31") (pinfunction "P2.4/T2RST/RXD1/HSI.2_31") (pintype "passive"))
    )
    (net (code "101") (name "unconnected-(D8-P2.5{slash}PWM.0{slash}HSO.5-Pad32)") (class "Default")
      (node (ref "D8") (pin "32") (pinfunction "P2.5/PWM.0/HSO.5_32") (pintype "passive"))
    )
    (net (code "102") (name "unconnected-(D8-P2.6{slash}T2UPDN{slash}TXD1-Pad36)") (class "Default")
      (node (ref "D8") (pin "36") (pinfunction "P2.6/T2UPDN/TXD1_36") (pintype "passive"))
    )
    (net (code "103") (name "unconnected-(D8-P2.7{slash}T2CAP{slash}HSI.3{slash}SDA-Pad37)") (class "Default")
      (node (ref "D8") (pin "37") (pinfunction "P2.7/T2CAP/HSI.3/SDA_37") (pintype "passive"))
    )
    (net (code "104") (name "unconnected-(D8-P3.0{slash}AD0-Pad67)") (class "Default")
      (node (ref "D8") (pin "67") (pinfunction "P3.0/AD0_67") (pintype "passive"))
    )
    (net (code "105") (name "unconnected-(D8-P3.1{slash}AD1-Pad66)") (class "Default")
      (node (ref "D8") (pin "66") (pinfunction "P3.1/AD1_66") (pintype "passive"))
    )
    (net (code "106") (name "unconnected-(D8-P3.2{slash}AD2-Pad65)") (class "Default")
      (node (ref "D8") (pin "65") (pinfunction "P3.2/AD2_65") (pintype "passive"))
    )
    (net (code "107") (name "unconnected-(D8-P3.3{slash}AD3-Pad63)") (class "Default")
      (node (ref "D8") (pin "63") (pinfunction "P3.3/AD3_63") (pintype "passive"))
    )
    (net (code "108") (name "unconnected-(D8-P3.4{slash}AD4-Pad62)") (class "Default")
      (node (ref "D8") (pin "62") (pinfunction "P3.4/AD4_62") (pintype "passive"))
    )
    (net (code "109") (name "unconnected-(D8-P3.5{slash}AD5-Pad61)") (class "Default")
      (node (ref "D8") (pin "61") (pinfunction "P3.5/AD5_61") (pintype "passive"))
    )
    (net (code "110") (name "unconnected-(D8-P3.6{slash}AD6-Pad59)") (class "Default")
      (node (ref "D8") (pin "59") (pinfunction "P3.6/AD6_59") (pintype "passive"))
    )
    (net (code "111") (name "unconnected-(D8-P3.7{slash}AD7-Pad58)") (class "Default")
      (node (ref "D8") (pin "58") (pinfunction "P3.7/AD7_58") (pintype "passive"))
    )
    (net (code "112") (name "unconnected-(D8-P4.0{slash}AD8-Pad52)") (class "Default")
      (node (ref "D8") (pin "52") (pinfunction "P4.0/AD8_52") (pintype "passive"))
    )
    (net (code "113") (name "unconnected-(D8-P4.1{slash}AD9-Pad51)") (class "Default")
      (node (ref "D8") (pin "51") (pinfunction "P4.1/AD9_51") (pintype "passive"))
    )
    (net (code "114") (name "unconnected-(D8-P4.2{slash}AD10-Pad50)") (class "Default")
      (node (ref "D8") (pin "50") (pinfunction "P4.2/AD10_50") (pintype "passive"))
    )
    (net (code "115") (name "unconnected-(D8-P4.3{slash}AD11-Pad49)") (class "Default")
      (node (ref "D8") (pin "49") (pinfunction "P4.3/AD11_49") (pintype "passive"))
    )
    (net (code "116") (name "unconnected-(D8-P4.4{slash}AD12-Pad48)") (class "Default")
      (node (ref "D8") (pin "48") (pinfunction "P4.4/AD12_48") (pintype "passive"))
    )
    (net (code "117") (name "unconnected-(D8-P4.5{slash}AD13-Pad47)") (class "Default")
      (node (ref "D8") (pin "47") (pinfunction "P4.5/AD13_47") (pintype "passive"))
    )
    (net (code "118") (name "unconnected-(D8-P4.6{slash}AD14-Pad46)") (class "Default")
      (node (ref "D8") (pin "46") (pinfunction "P4.6/AD14_46") (pintype "passive"))
    )
    (net (code "119") (name "unconnected-(D8-P4.7{slash}AD15-Pad45)") (class "Default")
      (node (ref "D8") (pin "45") (pinfunction "P4.7/AD15_45") (pintype "passive"))
    )
    (net (code "120") (name "unconnected-(D8-P5.0{slash}ACH8{slash}ACHN0-Pad81)") (class "Default")
      (node (ref "D8") (pin "81") (pinfunction "P5.0/ACH8/ACHN0_81") (pintype "passive"))
    )
    (net (code "121") (name "unconnected-(D8-P5.1{slash}ACH9{slash}ACHN1-Pad83)") (class "Default")
      (node (ref "D8") (pin "83") (pinfunction "P5.1/ACH9/ACHN1_83") (pintype "passive"))
    )
    (net (code "122") (name "unconnected-(D8-P5.2{slash}ACH10{slash}ACHN2-Pad7)") (class "Default")
      (node (ref "D8") (pin "7") (pinfunction "P5.2/ACH10/ACHN2_7") (pintype "passive"))
    )
    (net (code "123") (name "unconnected-(D8-P5.3{slash}ACH11{slash}ACHN3-Pad88)") (class "Default")
      (node (ref "D8") (pin "88") (pinfunction "P5.3/ACH11/ACHN3_88") (pintype "passive"))
    )
    (net (code "124") (name "unconnected-(D8-P5.4{slash}ACH12{slash}ACHN4-Pad2)") (class "Default")
      (node (ref "D8") (pin "2") (pinfunction "P5.4/ACH12/ACHN4_2") (pintype "passive"))
    )
    (net (code "125") (name "unconnected-(D8-P5.5{slash}ACH13{slash}ACHN5-Pad5)") (class "Default")
      (node (ref "D8") (pin "5") (pinfunction "P5.5/ACH13/ACHN5_5") (pintype "passive"))
    )
    (net (code "126") (name "unconnected-(D8-P5.6{slash}ACH14{slash}ACHN6-Pad85)") (class "Default")
      (node (ref "D8") (pin "85") (pinfunction "P5.6/ACH14/ACHN6_85") (pintype "passive"))
    )
    (net (code "127") (name "unconnected-(D8-P5.7{slash}ACH15{slash}ACHN7-Pad9)") (class "Default")
      (node (ref "D8") (pin "9") (pinfunction "P5.7/ACH15/ACHN7_9") (pintype "passive"))
    )
    (net (code "128") (name "unconnected-(D8-PWM.1-Pad22)") (class "Default")
      (node (ref "D8") (pin "22") (pinfunction "PWM.1_22") (pintype "passive"))
    )
    (net (code "129") (name "unconnected-(D8-PWM.2-Pad14)") (class "Default")
      (node (ref "D8") (pin "14") (pinfunction "PWM.2_14") (pintype "passive"))
    )
    (net (code "130") (name "unconnected-(D8-RD#-Pad68)") (class "Default")
      (node (ref "D8") (pin "68") (pinfunction "RD#_68") (pintype "passive"))
    )
    (net (code "131") (name "unconnected-(D8-READY-Pad43)") (class "Default")
      (node (ref "D8") (pin "43") (pinfunction "READY_43") (pintype "passive"))
    )
    (net (code "132") (name "unconnected-(D8-RESET#-Pad15)") (class "Default")
      (node (ref "D8") (pin "15") (pinfunction "RESET#_15") (pintype "passive"))
    )
    (net (code "133") (name "unconnected-(D8-VPR-Pad38)") (class "Default")
      (node (ref "D8") (pin "38") (pinfunction "VPR_38") (pintype "passive"))
    )
    (net (code "134") (name "unconnected-(D8-WR#{slash}WRL#-Pad40)") (class "Default")
      (node (ref "D8") (pin "40") (pinfunction "WR#/WRL#_40") (pintype "passive"))
    )
    (net (code "135") (name "unconnected-(D8-XTAL1-Pad74)") (class "Default")
      (node (ref "D8") (pin "74") (pinfunction "XTAL1_74") (pintype "passive"))
    )
    (net (code "136") (name "unconnected-(D8-XTAL2-Pad73)") (class "Default")
      (node (ref "D8") (pin "73") (pinfunction "XTAL2_73") (pintype "passive"))
    )
    (net (code "137") (name "unconnected-(D9-Pad1)") (class "Default")
      (node (ref "D9") (pin "1") (pinfunction "1_1") (pintype "passive"))
    )
    (net (code "138") (name "unconnected-(D9-Pad1)_1") (class "Default")
      (node (ref "D9") (pin "1") (pinfunction "1_1") (pintype "passive"))
    )
    (net (code "139") (name "unconnected-(D9-Pad2)") (class "Default")
      (node (ref "D9") (pin "2") (pinfunction "2_2") (pintype "passive"))
    )
    (net (code "140") (name "unconnected-(D9-Pad2)_1") (class "Default")
      (node (ref "D9") (pin "2") (pinfunction "2_2") (pintype "passive"))
    )
    (net (code "141") (name "unconnected-(D9-Pad7)") (class "Default")
      (node (ref "D9") (pin "7") (pinfunction "7_7") (pintype "passive"))
    )
    (net (code "142") (name "unconnected-(D9-Pad7)_1") (class "Default")
      (node (ref "D9") (pin "7") (pinfunction "7_7") (pintype "passive"))
    )
    (net (code "143") (name "unconnected-(D9-Pad8)") (class "Default")
      (node (ref "D9") (pin "8") (pinfunction "8_8") (pintype "passive"))
    )
    (net (code "144") (name "unconnected-(D9-Pad8)_1") (class "Default")
      (node (ref "D9") (pin "8") (pinfunction "8_8") (pintype "passive"))
    )
    (net (code "145") (name "unconnected-(D9-Pad9)") (class "Default")
      (node (ref "D9") (pin "9") (pinfunction "9_9") (pintype "passive"))
    )
    (net (code "146") (name "unconnected-(D9-Pad9)_1") (class "Default")
      (node (ref "D9") (pin "9") (pinfunction "9_9") (pintype "passive"))
    )
    (net (code "147") (name "unconnected-(D9-Pad10)") (class "Default")
      (node (ref "D9") (pin "10") (pinfunction "10_10") (pintype "passive"))
    )
    (net (code "148") (name "unconnected-(D9-Pad10)_1") (class "Default")
      (node (ref "D9") (pin "10") (pinfunction "10_10") (pintype "passive"))
    )
    (net (code "149") (name "unconnected-(D9-Pad15)") (class "Default")
      (node (ref "D9") (pin "15") (pinfunction "15_15") (pintype "passive"))
    )
    (net (code "150") (name "unconnected-(D9-Pad15)_1") (class "Default")
      (node (ref "D9") (pin "15") (pinfunction "15_15") (pintype "passive"))
    )
    (net (code "151") (name "unconnected-(D9-Pad16)") (class "Default")
      (node (ref "D9") (pin "16") (pinfunction "16_16") (pintype "passive"))
    )
    (net (code "152") (name "unconnected-(D9-Pad16)_1") (class "Default")
      (node (ref "D9") (pin "16") (pinfunction "16_16") (pintype "passive"))
    )
    (net (code "153") (name "unconnected-(D11-Pad1)") (class "Default")
      (node (ref "D11") (pin "1") (pinfunction "1_1") (pintype "passive"))
    )
    (net (code "154") (name "unconnected-(D11-Pad1)_1") (class "Default")
      (node (ref "D11") (pin "1") (pinfunction "1_1") (pintype "passive"))
    )
    (net (code "155") (name "unconnected-(D11-Pad2)") (class "Default")
      (node (ref "D11") (pin "2") (pinfunction "2_2") (pintype "passive"))
    )
    (net (code "156") (name "unconnected-(D11-Pad2)_1") (class "Default")
      (node (ref "D11") (pin "2") (pinfunction "2_2") (pintype "passive"))
    )
    (net (code "157") (name "unconnected-(D11-Pad7)") (class "Default")
      (node (ref "D11") (pin "7") (pinfunction "7_7") (pintype "passive"))
    )
    (net (code "158") (name "unconnected-(D11-Pad7)_1") (class "Default")
      (node (ref "D11") (pin "7") (pinfunction "7_7") (pintype "passive"))
    )
    (net (code "159") (name "unconnected-(D11-Pad8)") (class "Default")
      (node (ref "D11") (pin "8") (pinfunction "8_8") (pintype "passive"))
    )
    (net (code "160") (name "unconnected-(D11-Pad8)_1") (class "Default")
      (node (ref "D11") (pin "8") (pinfunction "8_8") (pintype "passive"))
    )
    (net (code "161") (name "unconnected-(D11-Pad9)") (class "Default")
      (node (ref "D11") (pin "9") (pinfunction "9_9") (pintype "passive"))
    )
    (net (code "162") (name "unconnected-(D11-Pad9)_1") (class "Default")
      (node (ref "D11") (pin "9") (pinfunction "9_9") (pintype "passive"))
    )
    (net (code "163") (name "unconnected-(D11-Pad10)") (class "Default")
      (node (ref "D11") (pin "10") (pinfunction "10_10") (pintype "passive"))
    )
    (net (code "164") (name "unconnected-(D11-Pad10)_1") (class "Default")
      (node (ref "D11") (pin "10") (pinfunction "10_10") (pintype "passive"))
    )
    (net (code "165") (name "unconnected-(D11-Pad15)") (class "Default")
      (node (ref "D11") (pin "15") (pinfunction "15_15") (pintype "passive"))
    )
    (net (code "166") (name "unconnected-(D11-Pad15)_1") (class "Default")
      (node (ref "D11") (pin "15") (pinfunction "15_15") (pintype "passive"))
    )
    (net (code "167") (name "unconnected-(D11-Pad16)") (class "Default")
      (node (ref "D11") (pin "16") (pinfunction "16_16") (pintype "passive"))
    )
    (net (code "168") (name "unconnected-(D11-Pad16)_1") (class "Default")
      (node (ref "D11") (pin "16") (pinfunction "16_16") (pintype "passive"))
    )
    (net (code "169") (name "unconnected-(D12-Pad1)") (class "Default")
      (node (ref "D12") (pin "1") (pinfunction "1_1") (pintype "passive"))
    )
    (net (code "170") (name "unconnected-(D12-Pad1)_1") (class "Default")
      (node (ref "D12") (pin "1") (pinfunction "1_1") (pintype "passive"))
    )
    (net (code "171") (name "unconnected-(D12-Pad2)") (class "Default")
      (node (ref "D12") (pin "2") (pinfunction "2_2") (pintype "passive"))
    )
    (net (code "172") (name "unconnected-(D12-Pad2)_1") (class "Default")
      (node (ref "D12") (pin "2") (pinfunction "2_2") (pintype "passive"))
    )
    (net (code "173") (name "unconnected-(D12-Pad7)") (class "Default")
      (node (ref "D12") (pin "7") (pinfunction "7_7") (pintype "passive"))
    )
    (net (code "174") (name "unconnected-(D12-Pad7)_1") (class "Default")
      (node (ref "D12") (pin "7") (pinfunction "7_7") (pintype "passive"))
    )
    (net (code "175") (name "unconnected-(D12-Pad8)") (class "Default")
      (node (ref "D12") (pin "8") (pinfunction "8_8") (pintype "passive"))
    )
    (net (code "176") (name "unconnected-(D12-Pad8)_1") (class "Default")
      (node (ref "D12") (pin "8") (pinfunction "8_8") (pintype "passive"))
    )
    (net (code "177") (name "unconnected-(D12-Pad9)") (class "Default")
      (node (ref "D12") (pin "9") (pinfunction "9_9") (pintype "passive"))
    )
    (net (code "178") (name "unconnected-(D12-Pad9)_1") (class "Default")
      (node (ref "D12") (pin "9") (pinfunction "9_9") (pintype "passive"))
    )
    (net (code "179") (name "unconnected-(D12-Pad10)") (class "Default")
      (node (ref "D12") (pin "10") (pinfunction "10_10") (pintype "passive"))
    )
    (net (code "180") (name "unconnected-(D12-Pad10)_1") (class "Default")
      (node (ref "D12") (pin "10") (pinfunction "10_10") (pintype "passive"))
    )
    (net (code "181") (name "unconnected-(D12-Pad15)") (class "Default")
      (node (ref "D12") (pin "15") (pinfunction "15_15") (pintype "passive"))
    )
    (net (code "182") (name "unconnected-(D12-Pad15)_1") (class "Default")
      (node (ref "D12") (pin "15") (pinfunction "15_15") (pintype "passive"))
    )
    (net (code "183") (name "unconnected-(D12-Pad16)") (class "Default")
      (node (ref "D12") (pin "16") (pinfunction "16_16") (pintype "passive"))
    )
    (net (code "184") (name "unconnected-(D12-Pad16)_1") (class "Default")
      (node (ref "D12") (pin "16") (pinfunction "16_16") (pintype "passive"))
    )
    (net (code "185") (name "unconnected-(D13-Pad4)") (class "Default")
      (node (ref "D13") (pin "4") (pintype "passive"))
    )
  )
)
